# NMX-2017.net
KiCad netlist of a schematic drawn in EAGLE
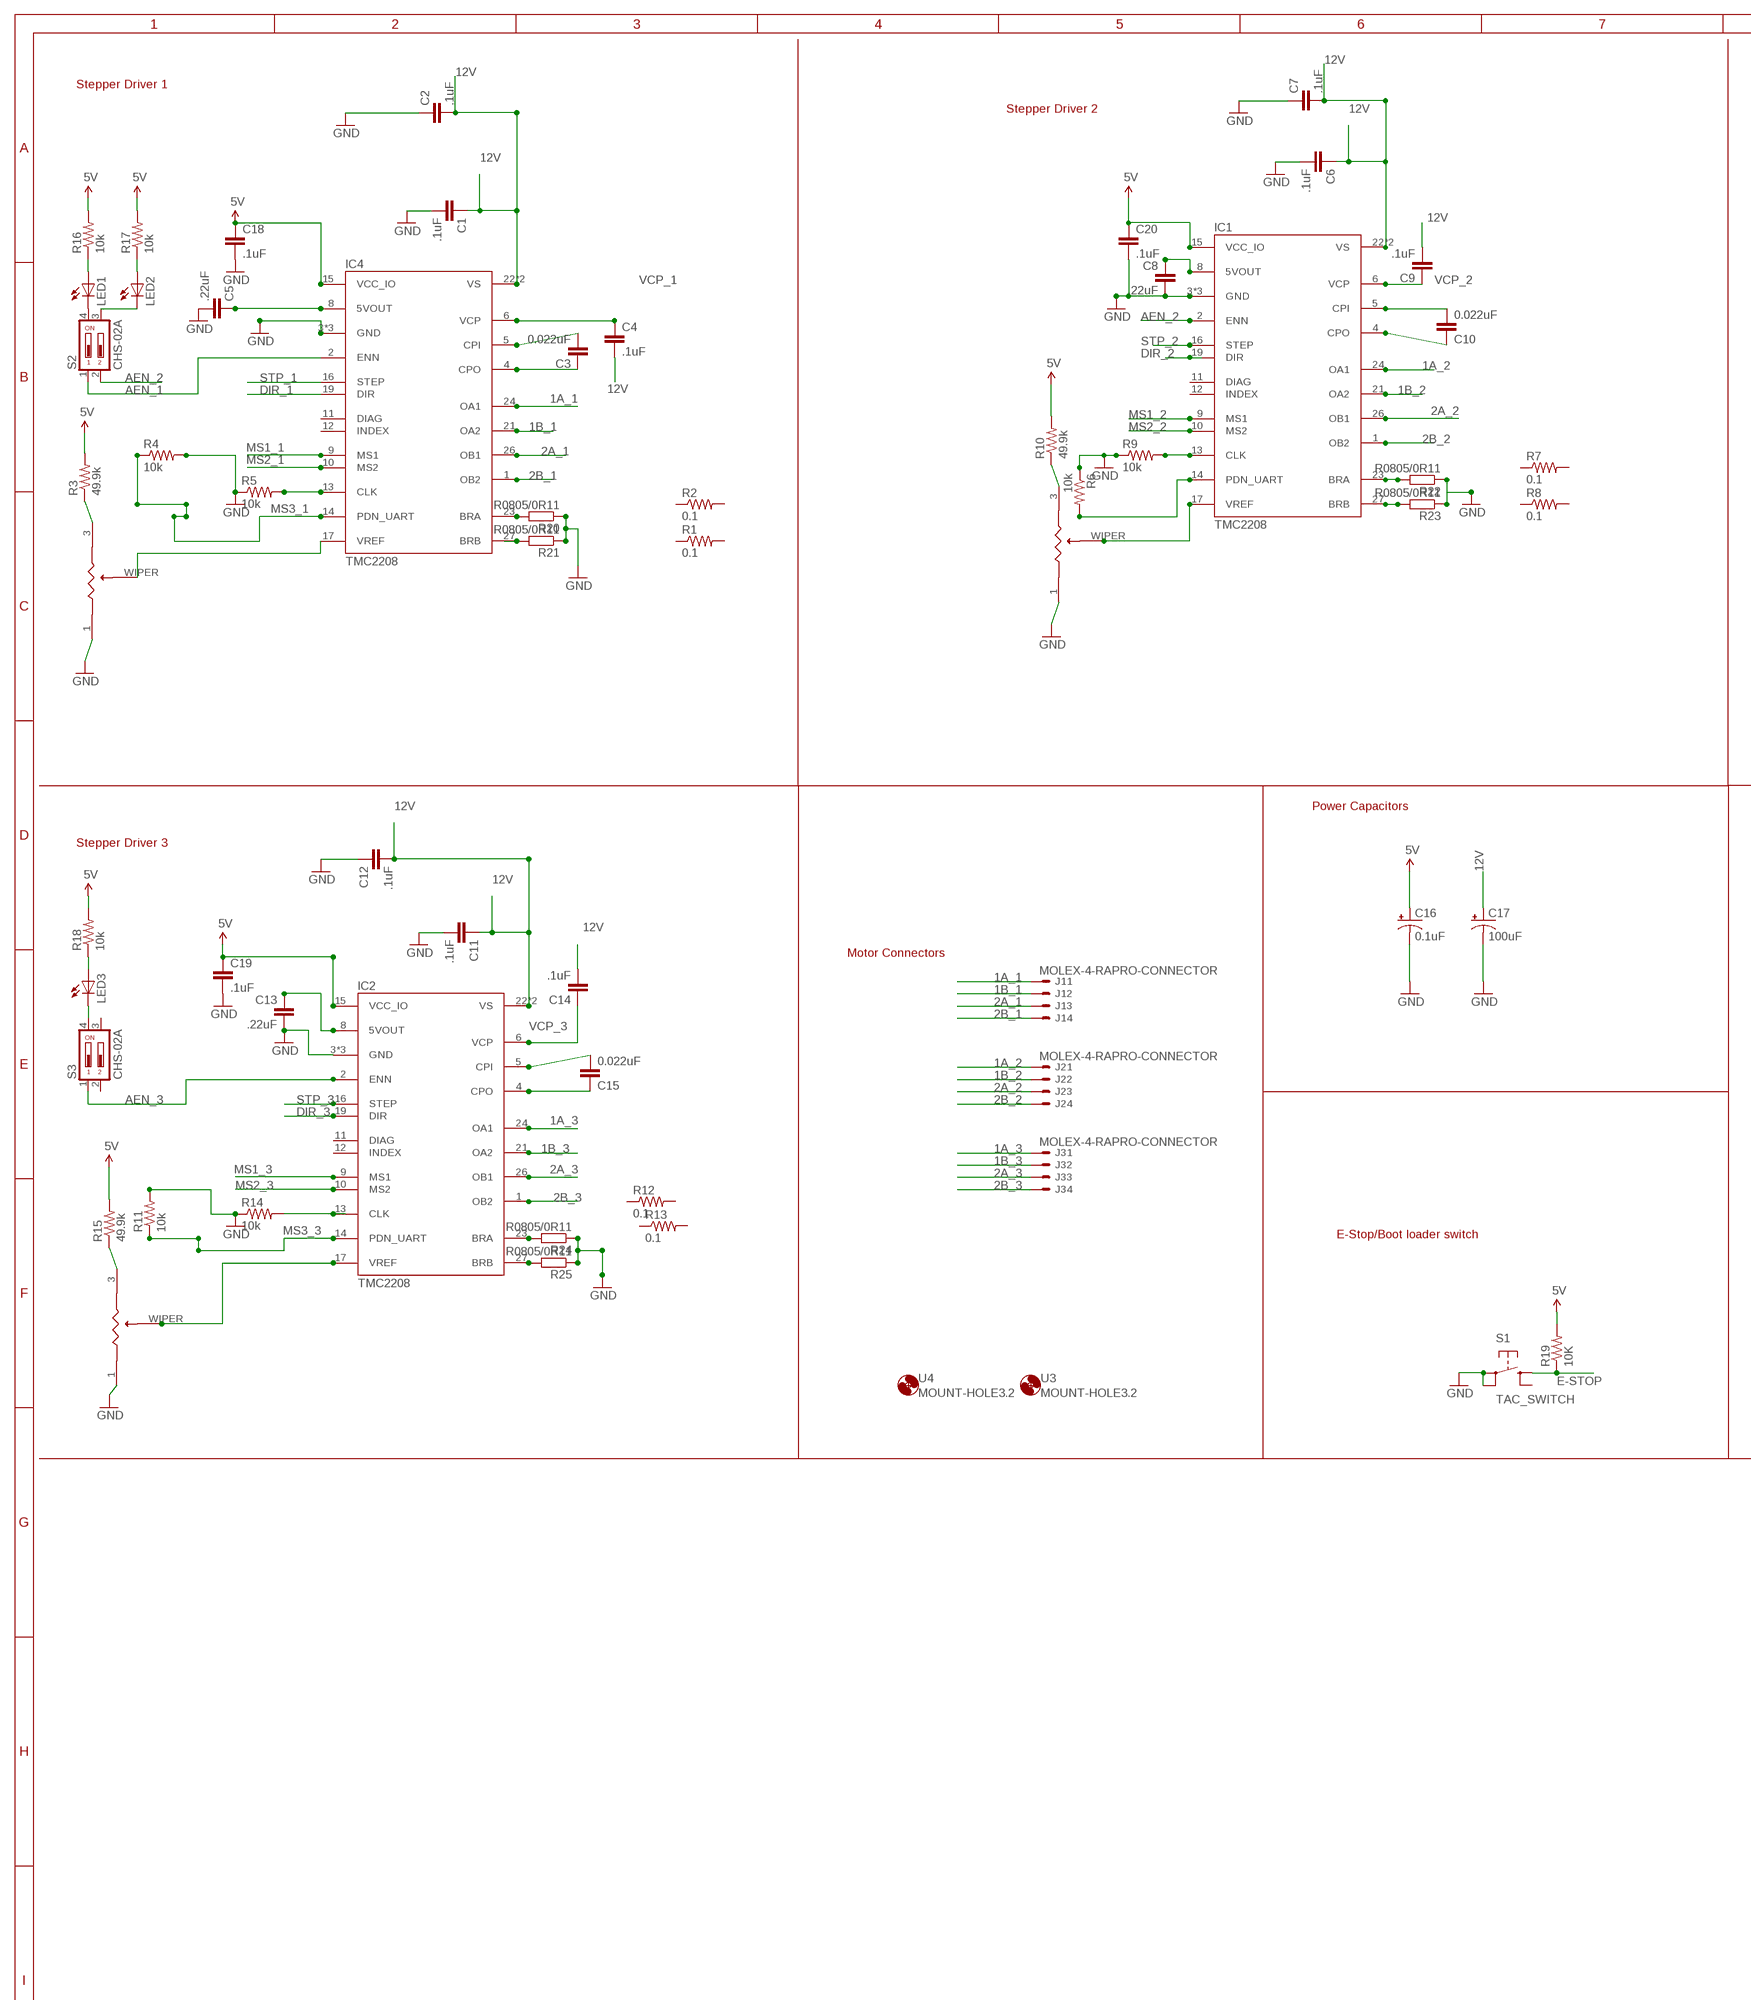
[diagram p0: schematic, sheet 1, part 1 of 2]
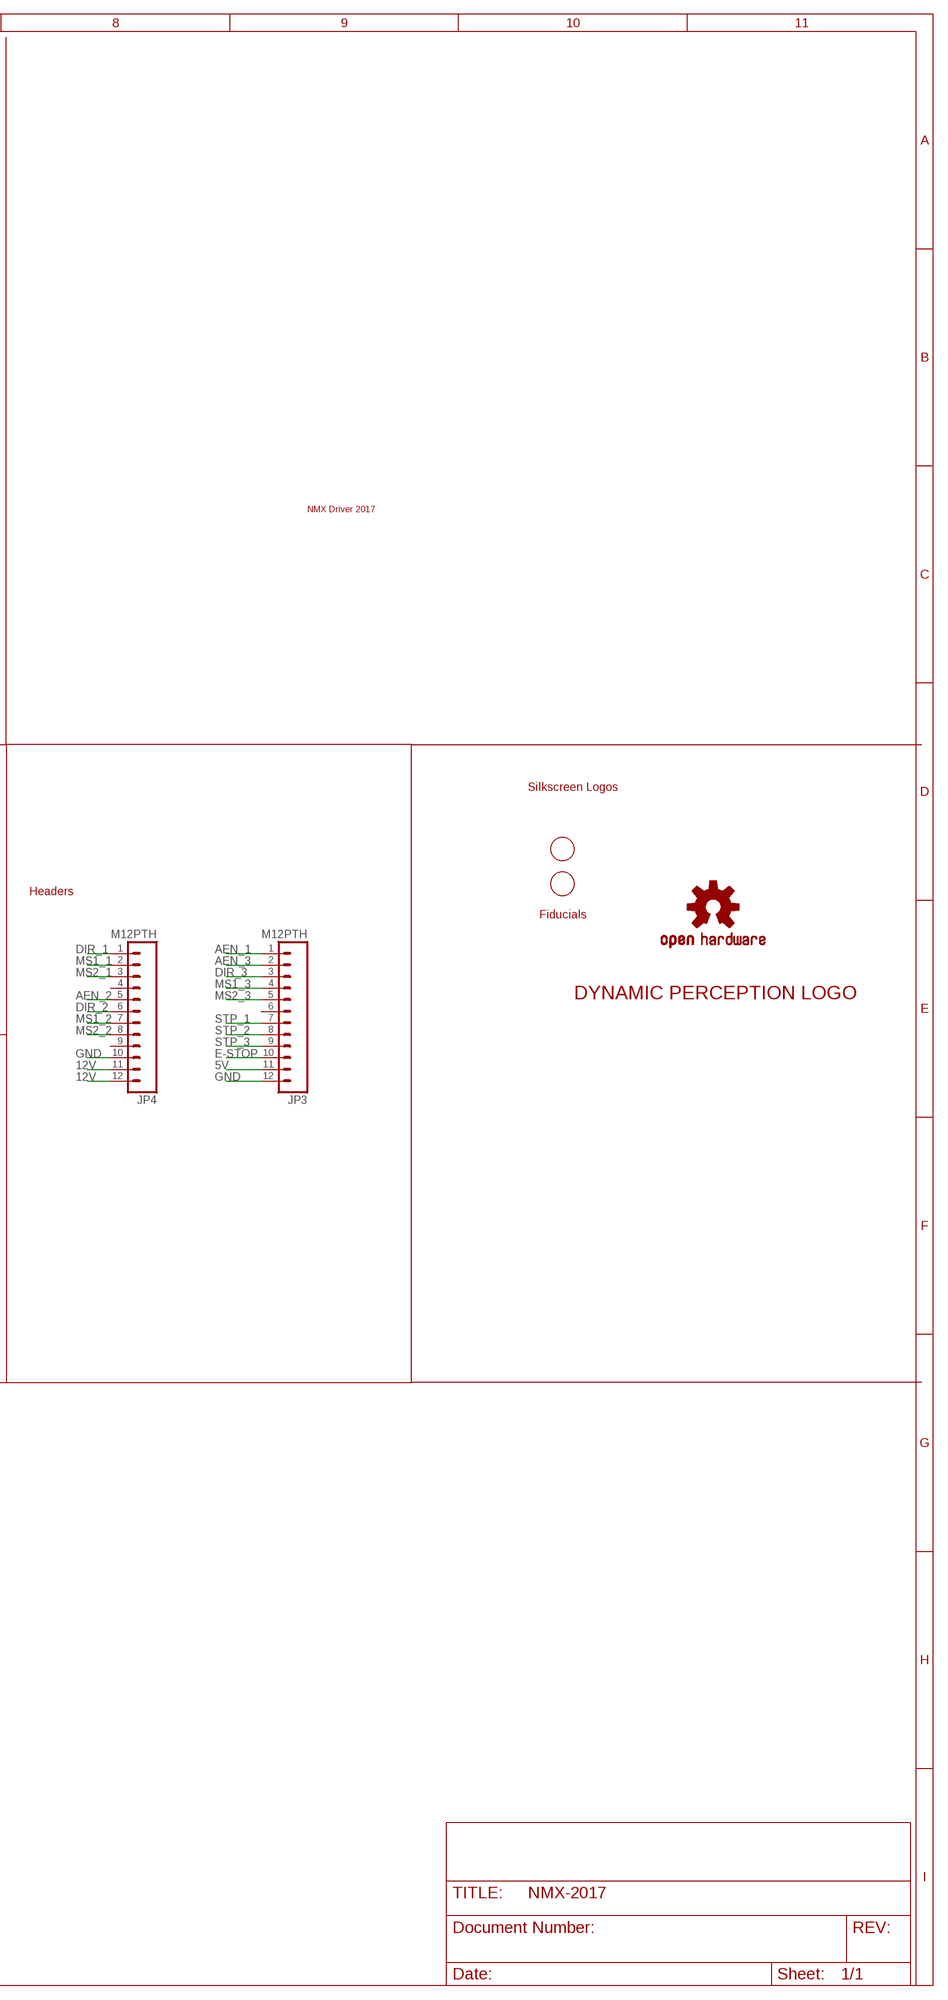
[diagram p1: schematic, sheet 1, part 2 of 2]

(export (version "E")
  (design (tool "Eeschema 10.0.6"))
  (components
    (comp (ref "C1")
      (value ".1uF")
      (footprint "eagle-import:0402-CAP")
      (fields (field (name "MF") "Taiyo Yuden") (field (name "MPN") "TMK105BJ104KV-F"))
      (libsource (lib "eagle-import") (part "CAP0402-CAP"))
    )
    (comp (ref "C2")
      (value ".1uF")
      (footprint "eagle-import:0402-CAP")
      (fields (field (name "MF") "Taiyo Yuden") (field (name "MPN") "TMK105BJ104KV-F"))
      (libsource (lib "eagle-import") (part "CAP0402-CAP"))
    )
    (comp (ref "C3")
      (value "0.022uF")
      (footprint "eagle-import:0402-CAP")
      (fields (field (name "MF") "Taiyo Yuden") (field (name "MPN") "TMK105BJ104KV-F"))
      (libsource (lib "eagle-import") (part "CAP0402-CAP"))
    )
    (comp (ref "C4")
      (value ".1uF")
      (footprint "eagle-import:0402-CAP")
      (fields (field (name "MF") "Taiyo Yuden") (field (name "MPN") "TMK105BJ104KV-F"))
      (libsource (lib "eagle-import") (part "CAP0402-CAP"))
    )
    (comp (ref "C5")
      (value ".22uF")
      (footprint "eagle-import:0402-CAP")
      (fields (field (name "MF") "Taiyo Yuden") (field (name "MPN") "TMK105BJ224KVHF"))
      (libsource (lib "eagle-import") (part "CAP0402-CAP"))
    )
    (comp (ref "C6")
      (value ".1uF")
      (footprint "eagle-import:0402-CAP")
      (fields (field (name "MF") "Taiyo Yuden") (field (name "MPN") "TMK105BJ104KV-F"))
      (libsource (lib "eagle-import") (part "CAP0402-CAP"))
    )
    (comp (ref "C7")
      (value ".1uF")
      (footprint "eagle-import:0402-CAP")
      (fields (field (name "MF") "Taiyo Yuden") (field (name "MPN") "TMK105BJ104KV-F"))
      (libsource (lib "eagle-import") (part "CAP0402-CAP"))
    )
    (comp (ref "C8")
      (value ".22uF")
      (footprint "eagle-import:0402-CAP")
      (fields (field (name "MF") "Taiyo Yuden") (field (name "MPN") "TMK105BJ224KVHF"))
      (libsource (lib "eagle-import") (part "CAP0402-CAP"))
    )
    (comp (ref "C9")
      (value ".1uF")
      (footprint "eagle-import:0402-CAP")
      (fields (field (name "MF") "Taiyo Yuden") (field (name "MPN") "TMK105BJ104KV-F"))
      (libsource (lib "eagle-import") (part "CAP0402-CAP"))
    )
    (comp (ref "C10")
      (value "0.022uF")
      (footprint "eagle-import:0402-CAP")
      (fields (field (name "MF") "Taiyo Yuden") (field (name "MPN") "TMK105BJ104KV-F"))
      (libsource (lib "eagle-import") (part "CAP0402-CAP"))
    )
    (comp (ref "C11")
      (value ".1uF")
      (footprint "eagle-import:0402-CAP")
      (fields (field (name "MF") "Taiyo Yuden") (field (name "MPN") "TMK105BJ104KV-F"))
      (libsource (lib "eagle-import") (part "CAP0402-CAP"))
    )
    (comp (ref "C12")
      (value ".1uF")
      (footprint "eagle-import:0402-CAP")
      (fields (field (name "MF") "Taiyo Yuden") (field (name "MPN") "TMK105BJ104KV-F"))
      (libsource (lib "eagle-import") (part "CAP0402-CAP"))
    )
    (comp (ref "C13")
      (value ".22uF")
      (footprint "eagle-import:0402-CAP")
      (fields (field (name "MF") "Taiyo Yuden") (field (name "MPN") "TMK105BJ224KVHF"))
      (libsource (lib "eagle-import") (part "CAP0402-CAP"))
    )
    (comp (ref "C14")
      (value ".1uF")
      (footprint "eagle-import:0402-CAP")
      (fields (field (name "MF") "Taiyo Yuden") (field (name "MPN") "TMK105BJ104KV-F"))
      (libsource (lib "eagle-import") (part "CAP0402-CAP"))
    )
    (comp (ref "C15")
      (value "0.022uF")
      (footprint "eagle-import:0402-CAP")
      (fields (field (name "MF") "Taiyo Yuden") (field (name "MPN") "TMK105BJ104KV-F"))
      (libsource (lib "eagle-import") (part "CAP0402-CAP"))
    )
    (comp (ref "C16")
      (value "0.1uF")
      (footprint "eagle-import:EIA3216")
      (fields (field (name "MF") "Kemet") (field (name "MPN") "T491A106M016AT"))
      (libsource (lib "eagle-import") (part "CAP_POL1206"))
    )
    (comp (ref "C17")
      (value "100uF")
      (footprint "eagle-import:PANASONIC_D")
      (fields (field (name "MF") "Panasonic Electronic Components") (field (name "MPN") "EEE-1EA101XP"))
      (libsource (lib "eagle-import") (part "CAP_POLD"))
    )
    (comp (ref "C18")
      (value ".1uF")
      (footprint "eagle-import:0402-CAP")
      (fields (field (name "MF") "Taiyo Yuden") (field (name "MPN") "TMK105BJ104KV-F"))
      (libsource (lib "eagle-import") (part "CAP0402-CAP"))
    )
    (comp (ref "C19")
      (value ".1uF")
      (footprint "eagle-import:0402-CAP")
      (fields (field (name "MF") "Taiyo Yuden") (field (name "MPN") "TMK105BJ104KV-F"))
      (libsource (lib "eagle-import") (part "CAP0402-CAP"))
    )
    (comp (ref "C20")
      (value ".1uF")
      (footprint "eagle-import:0402-CAP")
      (fields (field (name "MF") "Taiyo Yuden") (field (name "MPN") "TMK105BJ104KV-F"))
      (libsource (lib "eagle-import") (part "CAP0402-CAP"))
    )
    (comp (ref "IC1")
      (value "TMC2208")
      (footprint "eagle-import:QFN28-PAD")
      (libsource (lib "eagle-import") (part "TMC2208"))
    )
    (comp (ref "IC2")
      (value "TMC2208")
      (footprint "eagle-import:QFN28-PAD")
      (libsource (lib "eagle-import") (part "TMC2208"))
    )
    (comp (ref "IC4")
      (value "TMC2208")
      (footprint "eagle-import:QFN28-PAD")
      (libsource (lib "eagle-import") (part "TMC2208"))
    )
    (comp (ref "J1")
      (value "MOLEX-4-RAPRO-CONNECTOR")
      (footprint "eagle-import:PRO_CONNECTOR")
      (fields (field (name "MF") "Molex Inc") (field (name "MPN") "0022053041"))
      (libsource (lib "eagle-import") (part "MOLEX-4-RAPRO-CONNECTOR"))
    )
    (comp (ref "J2")
      (value "MOLEX-4-RAPRO-CONNECTOR")
      (footprint "eagle-import:PRO_CONNECTOR")
      (fields (field (name "MF") "Molex Inc") (field (name "MPN") "0022053041"))
      (libsource (lib "eagle-import") (part "MOLEX-4-RAPRO-CONNECTOR"))
    )
    (comp (ref "J3")
      (value "MOLEX-4-RAPRO-CONNECTOR")
      (footprint "eagle-import:PRO_CONNECTOR")
      (fields (field (name "MF") "Molex Inc") (field (name "MPN") "0022053041"))
      (libsource (lib "eagle-import") (part "MOLEX-4-RAPRO-CONNECTOR"))
    )
    (comp (ref "JP3")
      (value "M12PTH")
      (footprint "eagle-import:1X12")
      (fields (field (name "MF") "Molex Inc") (field (name "MPN") "0901200132"))
      (libsource (lib "eagle-import") (part "M12PTH"))
    )
    (comp (ref "JP4")
      (value "M12PTH")
      (footprint "eagle-import:1X12")
      (fields (field (name "MF") "Molex Inc") (field (name "MPN") "0901200132"))
      (libsource (lib "eagle-import") (part "M12PTH"))
    )
    (comp (ref "LED1")
      (value "LED0603")
      (footprint "eagle-import:LED-0603")
      (fields (field (name "MF") "OSRAM Opto Semiconductors Inc") (field (name "MPN") "LB Q39G-L2N2-35-1"))
      (libsource (lib "eagle-import") (part "LED0603"))
    )
    (comp (ref "LED2")
      (value "LED0603")
      (footprint "eagle-import:LED-0603")
      (fields (field (name "MF") "OSRAM Opto Semiconductors Inc") (field (name "MPN") "LB Q39G-L2N2-35-1"))
      (libsource (lib "eagle-import") (part "LED0603"))
    )
    (comp (ref "LED3")
      (value "LED0603")
      (footprint "eagle-import:LED-0603")
      (fields (field (name "MF") "OSRAM Opto Semiconductors Inc") (field (name "MPN") "LB Q39G-L2N2-35-1"))
      (libsource (lib "eagle-import") (part "LED0603"))
    )
    (comp (ref "R1")
      (value "0.1")
      (footprint "eagle-import:R0603")
      (fields (field (name "MF") "Samsung Electro-Mechanics America") (field (name "MPN") "RU1608FR100CS"))
      (libsource (lib "eagle-import") (part "R-US_R0603"))
    )
    (comp (ref "R2")
      (value "0.1")
      (footprint "eagle-import:R0603")
      (fields (field (name "MF") "Samsung Electro-Mechanics America") (field (name "MPN") "RU1608FR100CS"))
      (libsource (lib "eagle-import") (part "R-US_R0603"))
    )
    (comp (ref "R3")
      (value "49.9k")
      (footprint "eagle-import:R0402_BOTTOM")
      (fields (field (name "MF") "Yageo") (field (name "MPN") "RC0402FR-0749K9L"))
      (libsource (lib "eagle-import") (part "R-US_R0402_B"))
    )
    (comp (ref "R4")
      (value "10k")
      (footprint "eagle-import:R0402_BOTTOM")
      (fields (field (name "MF") "Yageo") (field (name "MPN") "RC0402FR-0720KL"))
      (libsource (lib "eagle-import") (part "R-US_R0402_B"))
    )
    (comp (ref "R5")
      (value "10k")
      (footprint "eagle-import:R0402_BOTTOM")
      (fields (field (name "MF") "Yageo") (field (name "MPN") "RC0402FR-0720KL"))
      (libsource (lib "eagle-import") (part "R-US_R0402_B"))
    )
    (comp (ref "R6")
      (value "10k")
      (footprint "eagle-import:R0402_BOTTOM")
      (fields (field (name "MF") "Yageo") (field (name "MPN") "RC0402FR-0720KL"))
      (libsource (lib "eagle-import") (part "R-US_R0402_B"))
    )
    (comp (ref "R7")
      (value "0.1")
      (footprint "eagle-import:R0603")
      (fields (field (name "MF") "Samsung Electro-Mechanics America") (field (name "MPN") "RU1608FR100CS"))
      (libsource (lib "eagle-import") (part "R-US_R0603"))
    )
    (comp (ref "R8")
      (value "0.1")
      (footprint "eagle-import:R0603")
      (fields (field (name "MF") "Samsung Electro-Mechanics America") (field (name "MPN") "RU1608FR100CS"))
      (libsource (lib "eagle-import") (part "R-US_R0603"))
    )
    (comp (ref "R9")
      (value "10k")
      (footprint "eagle-import:R0402_BOTTOM")
      (fields (field (name "MF") "Yageo") (field (name "MPN") "RC0402FR-0720KL"))
      (libsource (lib "eagle-import") (part "R-US_R0402_B"))
    )
    (comp (ref "R10")
      (value "49.9k")
      (footprint "eagle-import:R0402_BOTTOM")
      (fields (field (name "MF") "Yageo") (field (name "MPN") "RC0402FR-0749K9L"))
      (libsource (lib "eagle-import") (part "R-US_R0402_B"))
    )
    (comp (ref "R11")
      (value "10k")
      (footprint "eagle-import:R0402_BOTTOM")
      (fields (field (name "MF") "Yageo") (field (name "MPN") "RC0402FR-0720KL"))
      (libsource (lib "eagle-import") (part "R-US_R0402_B"))
    )
    (comp (ref "R12")
      (value "0.1")
      (footprint "eagle-import:R0603")
      (fields (field (name "MF") "Samsung Electro-Mechanics America") (field (name "MPN") "RU1608FR100CS"))
      (libsource (lib "eagle-import") (part "R-US_R0603"))
    )
    (comp (ref "R13")
      (value "0.1")
      (footprint "eagle-import:R0603")
      (fields (field (name "MF") "Samsung Electro-Mechanics America") (field (name "MPN") "RU1608FR100CS"))
      (libsource (lib "eagle-import") (part "R-US_R0603"))
    )
    (comp (ref "R14")
      (value "10k")
      (footprint "eagle-import:R0402_BOTTOM")
      (fields (field (name "MF") "Yageo") (field (name "MPN") "RC0402FR-0720KL"))
      (libsource (lib "eagle-import") (part "R-US_R0402_B"))
    )
    (comp (ref "R15")
      (value "49.9k")
      (footprint "eagle-import:R0402_BOTTOM")
      (fields (field (name "MF") "Yageo") (field (name "MPN") "RC0402FR-0749K9L"))
      (libsource (lib "eagle-import") (part "R-US_R0402_B"))
    )
    (comp (ref "R16")
      (value "10k")
      (footprint "eagle-import:R0402_BOTTOM")
      (fields (field (name "MF") "Yageo") (field (name "MPN") "RC0402FR-0714KL"))
      (libsource (lib "eagle-import") (part "R-US_R0402_B"))
    )
    (comp (ref "R17")
      (value "10k")
      (footprint "eagle-import:R0402_BOTTOM")
      (fields (field (name "MF") "Yageo") (field (name "MPN") "RC0402FR-0714KL"))
      (libsource (lib "eagle-import") (part "R-US_R0402_B"))
    )
    (comp (ref "R18")
      (value "10k")
      (footprint "eagle-import:R0402_BOTTOM")
      (fields (field (name "MF") "Yageo") (field (name "MPN") "RC0402FR-0714KL"))
      (libsource (lib "eagle-import") (part "R-US_R0402_B"))
    )
    (comp (ref "R19")
      (value "10K")
      (footprint "eagle-import:R0402_BOTTOM")
      (fields (field (name "MF") "Yageo") (field (name "MPN") "RC0402FR-0710KL"))
      (libsource (lib "eagle-import") (part "R-US_R0402_B"))
    )
    (comp (ref "R20")
      (value "R0805/0R11")
      (footprint "eagle-import:M0805")
      (libsource (lib "eagle-import") (part "R-EU_M0805"))
    )
    (comp (ref "R21")
      (value "R0805/0R11")
      (footprint "eagle-import:M0805")
      (libsource (lib "eagle-import") (part "R-EU_M0805"))
    )
    (comp (ref "R22")
      (value "R0805/0R11")
      (footprint "eagle-import:M0805")
      (libsource (lib "eagle-import") (part "R-EU_M0805"))
    )
    (comp (ref "R23")
      (value "R0805/0R11")
      (footprint "eagle-import:M0805")
      (libsource (lib "eagle-import") (part "R-EU_M0805"))
    )
    (comp (ref "R24")
      (value "R0805/0R11")
      (footprint "eagle-import:M0805")
      (libsource (lib "eagle-import") (part "R-EU_M0805"))
    )
    (comp (ref "R25")
      (value "R0805/0R11")
      (footprint "eagle-import:M0805")
      (libsource (lib "eagle-import") (part "R-EU_M0805"))
    )
    (comp (ref "S1")
      (value "TAC_SWITCH")
      (footprint "eagle-import:TAC_SWITCH_THR")
      (fields (field (name "MF") "TE Connectivity") (field (name "MPN") "2-1825027-0"))
      (libsource (lib "eagle-import") (part "TAC_SWITCH"))
    )
    (comp (ref "S2")
      (value "CHS-02A")
      (footprint "eagle-import:CHS-02A")
      (libsource (lib "eagle-import") (part "CHS-02A"))
    )
    (comp (ref "S3")
      (value "CHS-02A")
      (footprint "eagle-import:CHS-02A")
      (libsource (lib "eagle-import") (part "CHS-02A"))
    )
    (comp (ref "U$1")
      (value "DP_LOGOMICRO")
      (footprint "eagle-import:DP_LOGO_MICRO")
      (libsource (lib "eagle-import") (part "DP_LOGOMICRO"))
    )
    (comp (ref "U$2")
      (value "OSHW-LOGOS")
      (footprint "eagle-import:OSHW-LOGO-S")
      (libsource (lib "eagle-import") (part "OSHW-LOGOS"))
    )
    (comp (ref "U$3")
      (value "FIDUCIAL")
      (footprint "eagle-import:FIDUCIAL_1MM")
      (libsource (lib "eagle-import") (part "FIDUCIAL"))
    )
    (comp (ref "U$4")
      (value "FIDUCIAL")
      (footprint "eagle-import:FIDUCIAL_1MM")
      (libsource (lib "eagle-import") (part "FIDUCIAL"))
    )
    (comp (ref "U1")
      (value "CADJ")
      (footprint "eagle-import:3MM_SMD")
      (fields (field (name "MF") "Bourns Inc") (field (name "MPN") "TC33X-2-103E"))
      (libsource (lib "eagle-import") (part "TC33X-2"))
    )
    (comp (ref "U2")
      (value "CADJ")
      (footprint "eagle-import:3MM_SMD")
      (fields (field (name "MF") "Bourns Inc") (field (name "MPN") "TC33X-2-103E"))
      (libsource (lib "eagle-import") (part "TC33X-2"))
    )
    (comp (ref "U3")
      (value "MOUNT-HOLE3.2")
      (footprint "eagle-import:3,2")
      (libsource (lib "eagle-import") (part "MOUNT-HOLE3.2"))
    )
    (comp (ref "U4")
      (value "MOUNT-HOLE3.2")
      (footprint "eagle-import:3,2")
      (libsource (lib "eagle-import") (part "MOUNT-HOLE3.2"))
    )
    (comp (ref "U5")
      (value "CADJ")
      (footprint "eagle-import:3MM_SMD")
      (fields (field (name "MF") "Bourns Inc") (field (name "MPN") "TC33X-2-103E"))
      (libsource (lib "eagle-import") (part "TC33X-2"))
    )
  )
  (nets
    (net (code "1") (name "/1A_1") (class "Default")
      (node (ref "IC4") (pin "24") (pinfunction "OA1_24") (pintype "output"))
      (node (ref "J1") (pin "P$1") (pinfunction "S_P$1") (pintype "passive"))
    )
    (net (code "2") (name "/1A_2") (class "Default")
      (node (ref "IC1") (pin "24") (pinfunction "OA1_24") (pintype "output"))
      (node (ref "J2") (pin "P$1") (pinfunction "S_P$1") (pintype "passive"))
    )
    (net (code "3") (name "/1A_3") (class "Default")
      (node (ref "IC2") (pin "24") (pinfunction "OA1_24") (pintype "output"))
      (node (ref "J3") (pin "P$1") (pinfunction "S_P$1") (pintype "passive"))
    )
    (net (code "4") (name "/1B_1") (class "Default")
      (node (ref "IC4") (pin "21") (pinfunction "OA2_21") (pintype "output"))
      (node (ref "J1") (pin "P$2") (pinfunction "S_P$2") (pintype "passive"))
    )
    (net (code "5") (name "/1B_2") (class "Default")
      (node (ref "IC1") (pin "21") (pinfunction "OA2_21") (pintype "output"))
      (node (ref "J2") (pin "P$2") (pinfunction "S_P$2") (pintype "passive"))
    )
    (net (code "6") (name "/1B_3") (class "Default")
      (node (ref "IC2") (pin "21") (pinfunction "OA2_21") (pintype "output"))
      (node (ref "J3") (pin "P$2") (pinfunction "S_P$2") (pintype "passive"))
    )
    (net (code "7") (name "/2A_1") (class "Default")
      (node (ref "IC4") (pin "26") (pinfunction "OB1_26") (pintype "output"))
      (node (ref "J1") (pin "P$3") (pinfunction "S_P$3") (pintype "passive"))
    )
    (net (code "8") (name "/2A_2") (class "Default")
      (node (ref "IC1") (pin "26") (pinfunction "OB1_26") (pintype "output"))
      (node (ref "J2") (pin "P$3") (pinfunction "S_P$3") (pintype "passive"))
    )
    (net (code "9") (name "/2A_3") (class "Default")
      (node (ref "IC2") (pin "26") (pinfunction "OB1_26") (pintype "output"))
      (node (ref "J3") (pin "P$3") (pinfunction "S_P$3") (pintype "passive"))
    )
    (net (code "10") (name "/2B_1") (class "Default")
      (node (ref "IC4") (pin "1") (pinfunction "OB2_1") (pintype "output"))
      (node (ref "J1") (pin "P$4") (pinfunction "S_P$4") (pintype "passive"))
    )
    (net (code "11") (name "/2B_2") (class "Default")
      (node (ref "IC1") (pin "1") (pinfunction "OB2_1") (pintype "output"))
      (node (ref "J2") (pin "P$4") (pinfunction "S_P$4") (pintype "passive"))
    )
    (net (code "12") (name "/2B_3") (class "Default")
      (node (ref "IC2") (pin "1") (pinfunction "OB2_1") (pintype "output"))
      (node (ref "J3") (pin "P$4") (pinfunction "S_P$4") (pintype "passive"))
    )
    (net (code "13") (name "/12V") (class "Default")
      (node (ref "C1") (pin "1") (pinfunction "1_1") (pintype "passive"))
      (node (ref "C11") (pin "1") (pinfunction "1_1") (pintype "passive"))
      (node (ref "C12") (pin "2") (pinfunction "2_2") (pintype "passive"))
      (node (ref "C14") (pin "2") (pinfunction "2_2") (pintype "passive"))
      (node (ref "C17") (pin "+") (pinfunction "+_+") (pintype "passive"))
      (node (ref "C2") (pin "2") (pinfunction "2_2") (pintype "passive"))
      (node (ref "C4") (pin "2") (pinfunction "2_2") (pintype "passive"))
      (node (ref "C6") (pin "1") (pinfunction "1_1") (pintype "passive"))
      (node (ref "C7") (pin "2") (pinfunction "2_2") (pintype "passive"))
      (node (ref "C9") (pin "2") (pinfunction "2_2") (pintype "passive"))
      (node (ref "IC1") (pin "22") (pinfunction "VS_22") (pintype "power_in"))
      (node (ref "IC1") (pin "28") (pinfunction "VS_28") (pintype "power_in"))
      (node (ref "IC2") (pin "22") (pinfunction "VS_22") (pintype "power_in"))
      (node (ref "IC2") (pin "28") (pinfunction "VS_28") (pintype "power_in"))
      (node (ref "IC4") (pin "22") (pinfunction "VS_22") (pintype "power_in"))
      (node (ref "IC4") (pin "28") (pinfunction "VS_28") (pintype "power_in"))
      (node (ref "JP4") (pin "11") (pinfunction "11_11") (pintype "passive"))
      (node (ref "JP4") (pin "12") (pinfunction "12_12") (pintype "passive"))
    )
    (net (code "14") (name "/AEN_1") (class "Default")
      (node (ref "IC4") (pin "2") (pinfunction "ENN_2") (pintype "bidirectional"))
      (node (ref "JP3") (pin "1") (pinfunction "1_1") (pintype "passive"))
      (node (ref "S2") (pin "1") (pinfunction "1_1") (pintype "passive"))
    )
    (net (code "15") (name "/AEN_2") (class "Default")
      (node (ref "IC1") (pin "2") (pinfunction "ENN_2") (pintype "bidirectional"))
      (node (ref "JP4") (pin "5") (pinfunction "5_5") (pintype "passive"))
      (node (ref "S2") (pin "2") (pinfunction "2_2") (pintype "passive"))
    )
    (net (code "16") (name "/AEN_3") (class "Default")
      (node (ref "IC2") (pin "2") (pinfunction "ENN_2") (pintype "bidirectional"))
      (node (ref "JP3") (pin "2") (pinfunction "2_2") (pintype "passive"))
      (node (ref "S3") (pin "1") (pinfunction "1_1") (pintype "passive"))
    )
    (net (code "17") (name "/DIR_1") (class "Default")
      (node (ref "IC4") (pin "19") (pinfunction "DIR_19") (pintype "bidirectional"))
      (node (ref "JP4") (pin "1") (pinfunction "1_1") (pintype "passive"))
    )
    (net (code "18") (name "/DIR_2") (class "Default")
      (node (ref "IC1") (pin "19") (pinfunction "DIR_19") (pintype "bidirectional"))
      (node (ref "JP4") (pin "6") (pinfunction "6_6") (pintype "passive"))
    )
    (net (code "19") (name "/DIR_3") (class "Default")
      (node (ref "IC2") (pin "19") (pinfunction "DIR_19") (pintype "bidirectional"))
      (node (ref "JP3") (pin "3") (pinfunction "3_3") (pintype "passive"))
    )
    (net (code "20") (name "/E-STOP") (class "Default")
      (node (ref "JP3") (pin "10") (pinfunction "10_10") (pintype "passive"))
      (node (ref "R19") (pin "1") (pinfunction "1_1") (pintype "passive"))
      (node (ref "S1") (pin "B") (pinfunction "3_B") (pintype "passive"))
    )
    (net (code "21") (name "/MS1_1") (class "Default")
      (node (ref "IC4") (pin "9") (pinfunction "MS1_9") (pintype "bidirectional"))
      (node (ref "JP4") (pin "2") (pinfunction "2_2") (pintype "passive"))
    )
    (net (code "22") (name "/MS1_2") (class "Default")
      (node (ref "IC1") (pin "9") (pinfunction "MS1_9") (pintype "bidirectional"))
      (node (ref "JP4") (pin "7") (pinfunction "7_7") (pintype "passive"))
    )
    (net (code "23") (name "/MS1_3") (class "Default")
      (node (ref "IC2") (pin "9") (pinfunction "MS1_9") (pintype "bidirectional"))
      (node (ref "JP3") (pin "4") (pinfunction "4_4") (pintype "passive"))
    )
    (net (code "24") (name "/MS2_1") (class "Default")
      (node (ref "IC4") (pin "10") (pinfunction "MS2_10") (pintype "bidirectional"))
      (node (ref "JP4") (pin "3") (pinfunction "3_3") (pintype "passive"))
    )
    (net (code "25") (name "/MS2_2") (class "Default")
      (node (ref "IC1") (pin "10") (pinfunction "MS2_10") (pintype "bidirectional"))
      (node (ref "JP4") (pin "8") (pinfunction "8_8") (pintype "passive"))
    )
    (net (code "26") (name "/MS2_3") (class "Default")
      (node (ref "IC2") (pin "10") (pinfunction "MS2_10") (pintype "bidirectional"))
      (node (ref "JP3") (pin "5") (pinfunction "5_5") (pintype "passive"))
    )
    (net (code "27") (name "/MS3_1") (class "Default")
      (node (ref "IC4") (pin "14") (pinfunction "PDN_UART_14") (pintype "bidirectional"))
      (node (ref "R4") (pin "1") (pinfunction "1_1") (pintype "passive"))
    )
    (net (code "28") (name "/MS3_3") (class "Default")
      (node (ref "IC2") (pin "14") (pinfunction "PDN_UART_14") (pintype "bidirectional"))
      (node (ref "R11") (pin "1") (pinfunction "1_1") (pintype "passive"))
    )
    (net (code "29") (name "/STP_1") (class "Default")
      (node (ref "IC4") (pin "16") (pinfunction "STEP_16") (pintype "bidirectional"))
      (node (ref "JP3") (pin "7") (pinfunction "7_7") (pintype "passive"))
    )
    (net (code "30") (name "/STP_2") (class "Default")
      (node (ref "IC1") (pin "16") (pinfunction "STEP_16") (pintype "bidirectional"))
      (node (ref "JP3") (pin "8") (pinfunction "8_8") (pintype "passive"))
    )
    (net (code "31") (name "/STP_3") (class "Default")
      (node (ref "IC2") (pin "16") (pinfunction "STEP_16") (pintype "bidirectional"))
      (node (ref "JP3") (pin "9") (pinfunction "9_9") (pintype "passive"))
    )
    (net (code "32") (name "/VCP_1") (class "Default")
      (node (ref "C4") (pin "1") (pinfunction "1_1") (pintype "passive"))
      (node (ref "IC4") (pin "6") (pinfunction "VCP_6") (pintype "passive"))
    )
    (net (code "33") (name "/VCP_2") (class "Default")
      (node (ref "C9") (pin "1") (pinfunction "1_1") (pintype "passive"))
      (node (ref "IC1") (pin "6") (pinfunction "VCP_6") (pintype "passive"))
    )
    (net (code "34") (name "/VCP_3") (class "Default")
      (node (ref "C14") (pin "1") (pinfunction "1_1") (pintype "passive"))
      (node (ref "IC2") (pin "6") (pinfunction "VCP_6") (pintype "passive"))
    )
    (net (code "35") (name "5V") (class "Default")
      (node (ref "C16") (pin "A") (pinfunction "+_A") (pintype "passive"))
      (node (ref "C18") (pin "1") (pinfunction "1_1") (pintype "passive"))
      (node (ref "C19") (pin "1") (pinfunction "1_1") (pintype "passive"))
      (node (ref "C20") (pin "1") (pinfunction "1_1") (pintype "passive"))
      (node (ref "IC1") (pin "15") (pinfunction "VCC_IO_15") (pintype "power_in"))
      (node (ref "IC2") (pin "15") (pinfunction "VCC_IO_15") (pintype "power_in"))
      (node (ref "IC4") (pin "15") (pinfunction "VCC_IO_15") (pintype "power_in"))
      (node (ref "JP3") (pin "11") (pinfunction "11_11") (pintype "passive"))
      (node (ref "R10") (pin "2") (pinfunction "2_2") (pintype "passive"))
      (node (ref "R15") (pin "2") (pinfunction "2_2") (pintype "passive"))
      (node (ref "R16") (pin "2") (pinfunction "2_2") (pintype "passive"))
      (node (ref "R17") (pin "2") (pinfunction "2_2") (pintype "passive"))
      (node (ref "R18") (pin "2") (pinfunction "2_2") (pintype "passive"))
      (node (ref "R19") (pin "2") (pinfunction "2_2") (pintype "passive"))
      (node (ref "R3") (pin "2") (pinfunction "2_2") (pintype "passive"))
    )
    (net (code "36") (name "GND") (class "Default")
      (node (ref "C1") (pin "2") (pinfunction "2_2") (pintype "passive"))
      (node (ref "C11") (pin "2") (pinfunction "2_2") (pintype "passive"))
      (node (ref "C12") (pin "1") (pinfunction "1_1") (pintype "passive"))
      (node (ref "C13") (pin "2") (pinfunction "2_2") (pintype "passive"))
      (node (ref "C16") (pin "C") (pinfunction "-_C") (pintype "passive"))
      (node (ref "C17") (pin "-") (pinfunction "-_-") (pintype "passive"))
      (node (ref "C18") (pin "2") (pinfunction "2_2") (pintype "passive"))
      (node (ref "C19") (pin "2") (pinfunction "2_2") (pintype "passive"))
      (node (ref "C2") (pin "1") (pinfunction "1_1") (pintype "passive"))
      (node (ref "C20") (pin "2") (pinfunction "2_2") (pintype "passive"))
      (node (ref "C5") (pin "2") (pinfunction "2_2") (pintype "passive"))
      (node (ref "C6") (pin "2") (pinfunction "2_2") (pintype "passive"))
      (node (ref "C7") (pin "1") (pinfunction "1_1") (pintype "passive"))
      (node (ref "C8") (pin "2") (pinfunction "2_2") (pintype "passive"))
      (node (ref "IC1") (pin "18") (pinfunction "GND_18") (pintype "power_in"))
      (node (ref "IC1") (pin "3") (pinfunction "GND_3") (pintype "power_in"))
      (node (ref "IC1") (pin "TP") (pinfunction "GND_TP") (pintype "power_in"))
      (node (ref "IC2") (pin "18") (pinfunction "GND_18") (pintype "power_in"))
      (node (ref "IC2") (pin "3") (pinfunction "GND_3") (pintype "power_in"))
      (node (ref "IC2") (pin "TP") (pinfunction "GND_TP") (pintype "power_in"))
      (node (ref "IC4") (pin "18") (pinfunction "GND_18") (pintype "power_in"))
      (node (ref "IC4") (pin "3") (pinfunction "GND_3") (pintype "power_in"))
      (node (ref "IC4") (pin "TP") (pinfunction "GND_TP") (pintype "power_in"))
      (node (ref "JP3") (pin "12") (pinfunction "12_12") (pintype "passive"))
      (node (ref "JP4") (pin "10") (pinfunction "10_10") (pintype "passive"))
      (node (ref "R11") (pin "2") (pinfunction "2_2") (pintype "passive"))
      (node (ref "R14") (pin "1") (pinfunction "1_1") (pintype "passive"))
      (node (ref "R20") (pin "1") (pinfunction "1_1") (pintype "passive"))
      (node (ref "R21") (pin "1") (pinfunction "1_1") (pintype "passive"))
      (node (ref "R22") (pin "1") (pinfunction "1_1") (pintype "passive"))
      (node (ref "R23") (pin "1") (pinfunction "1_1") (pintype "passive"))
      (node (ref "R24") (pin "1") (pinfunction "1_1") (pintype "passive"))
      (node (ref "R25") (pin "1") (pinfunction "1_1") (pintype "passive"))
      (node (ref "R4") (pin "2") (pinfunction "2_2") (pintype "passive"))
      (node (ref "R5") (pin "1") (pinfunction "1_1") (pintype "passive"))
      (node (ref "R6") (pin "1") (pinfunction "1_1") (pintype "passive"))
      (node (ref "R9") (pin "1") (pinfunction "1_1") (pintype "passive"))
      (node (ref "S1") (pin "A") (pinfunction "1_A") (pintype "passive"))
      (node (ref "S1") (pin "P$1") (pinfunction "2_P$1") (pintype "passive"))
      (node (ref "U1") (pin "1") (pinfunction "1_1") (pintype "bidirectional"))
      (node (ref "U2") (pin "1") (pinfunction "1_1") (pintype "bidirectional"))
      (node (ref "U5") (pin "1") (pinfunction "1_1") (pintype "bidirectional"))
    )
    (net (code "37") (name "Net-(IC1-5VOUT)") (class "Default")
      (node (ref "C8") (pin "1") (pinfunction "1_1") (pintype "passive"))
      (node (ref "IC1") (pin "8") (pinfunction "5VOUT_8") (pintype "power_in"))
    )
    (net (code "38") (name "Net-(IC1-BRA)") (class "Default")
      (node (ref "IC1") (pin "23") (pinfunction "BRA_23") (pintype "output"))
      (node (ref "R22") (pin "2") (pinfunction "2_2") (pintype "passive"))
    )
    (net (code "39") (name "Net-(IC1-BRB)") (class "Default")
      (node (ref "IC1") (pin "27") (pinfunction "BRB_27") (pintype "output"))
      (node (ref "R23") (pin "2") (pinfunction "2_2") (pintype "passive"))
    )
    (net (code "40") (name "Net-(IC1-CLK)") (class "Default")
      (node (ref "IC1") (pin "13") (pinfunction "CLK_13") (pintype "bidirectional"))
      (node (ref "R9") (pin "2") (pinfunction "2_2") (pintype "passive"))
    )
    (net (code "41") (name "Net-(IC1-CPI)") (class "Default")
      (node (ref "C10") (pin "2") (pinfunction "2_2") (pintype "passive"))
      (node (ref "IC1") (pin "5") (pinfunction "CPI_5") (pintype "passive"))
    )
    (net (code "42") (name "Net-(IC1-CPO)") (class "Default")
      (node (ref "C10") (pin "1") (pinfunction "1_1") (pintype "passive"))
      (node (ref "IC1") (pin "4") (pinfunction "CPO_4") (pintype "passive"))
    )
    (net (code "43") (name "Net-(IC1-PDN_UART)") (class "Default")
      (node (ref "IC1") (pin "14") (pinfunction "PDN_UART_14") (pintype "bidirectional"))
      (node (ref "R6") (pin "2") (pinfunction "2_2") (pintype "passive"))
    )
    (net (code "44") (name "Net-(IC1-VREF)") (class "Default")
      (node (ref "IC1") (pin "17") (pinfunction "VREF_17") (pintype "passive"))
      (node (ref "U2") (pin "WIPER") (pinfunction "2_WIPER") (pintype "bidirectional"))
    )
    (net (code "45") (name "Net-(IC2-5VOUT)") (class "Default")
      (node (ref "C13") (pin "1") (pinfunction "1_1") (pintype "passive"))
      (node (ref "IC2") (pin "8") (pinfunction "5VOUT_8") (pintype "power_in"))
    )
    (net (code "46") (name "Net-(IC2-BRA)") (class "Default")
      (node (ref "IC2") (pin "23") (pinfunction "BRA_23") (pintype "output"))
      (node (ref "R24") (pin "2") (pinfunction "2_2") (pintype "passive"))
    )
    (net (code "47") (name "Net-(IC2-BRB)") (class "Default")
      (node (ref "IC2") (pin "27") (pinfunction "BRB_27") (pintype "output"))
      (node (ref "R25") (pin "2") (pinfunction "2_2") (pintype "passive"))
    )
    (net (code "48") (name "Net-(IC2-CLK)") (class "Default")
      (node (ref "IC2") (pin "13") (pinfunction "CLK_13") (pintype "bidirectional"))
      (node (ref "R14") (pin "2") (pinfunction "2_2") (pintype "passive"))
    )
    (net (code "49") (name "Net-(IC2-CPI)") (class "Default")
      (node (ref "C15") (pin "2") (pinfunction "2_2") (pintype "passive"))
      (node (ref "IC2") (pin "5") (pinfunction "CPI_5") (pintype "passive"))
    )
    (net (code "50") (name "Net-(IC2-CPO)") (class "Default")
      (node (ref "C15") (pin "1") (pinfunction "1_1") (pintype "passive"))
      (node (ref "IC2") (pin "4") (pinfunction "CPO_4") (pintype "passive"))
    )
    (net (code "51") (name "Net-(IC2-VREF)") (class "Default")
      (node (ref "IC2") (pin "17") (pinfunction "VREF_17") (pintype "passive"))
      (node (ref "U5") (pin "WIPER") (pinfunction "2_WIPER") (pintype "bidirectional"))
    )
    (net (code "52") (name "Net-(IC4-5VOUT)") (class "Default")
      (node (ref "C5") (pin "1") (pinfunction "1_1") (pintype "passive"))
      (node (ref "IC4") (pin "8") (pinfunction "5VOUT_8") (pintype "power_in"))
    )
    (net (code "53") (name "Net-(IC4-BRA)") (class "Default")
      (node (ref "IC4") (pin "23") (pinfunction "BRA_23") (pintype "output"))
      (node (ref "R20") (pin "2") (pinfunction "2_2") (pintype "passive"))
    )
    (net (code "54") (name "Net-(IC4-BRB)") (class "Default")
      (node (ref "IC4") (pin "27") (pinfunction "BRB_27") (pintype "output"))
      (node (ref "R21") (pin "2") (pinfunction "2_2") (pintype "passive"))
    )
    (net (code "55") (name "Net-(IC4-CLK)") (class "Default")
      (node (ref "IC4") (pin "13") (pinfunction "CLK_13") (pintype "bidirectional"))
      (node (ref "R5") (pin "2") (pinfunction "2_2") (pintype "passive"))
    )
    (net (code "56") (name "Net-(IC4-CPI)") (class "Default")
      (node (ref "C3") (pin "2") (pinfunction "2_2") (pintype "passive"))
      (node (ref "IC4") (pin "5") (pinfunction "CPI_5") (pintype "passive"))
    )
    (net (code "57") (name "Net-(IC4-CPO)") (class "Default")
      (node (ref "C3") (pin "1") (pinfunction "1_1") (pintype "passive"))
      (node (ref "IC4") (pin "4") (pinfunction "CPO_4") (pintype "passive"))
    )
    (net (code "58") (name "Net-(IC4-VREF)") (class "Default")
      (node (ref "IC4") (pin "17") (pinfunction "VREF_17") (pintype "passive"))
      (node (ref "U1") (pin "WIPER") (pinfunction "2_WIPER") (pintype "bidirectional"))
    )
    (net (code "59") (name "Net-(LED1-PadA)") (class "Default")
      (node (ref "LED1") (pin "A") (pinfunction "A_A") (pintype "passive"))
      (node (ref "R16") (pin "1") (pinfunction "1_1") (pintype "passive"))
    )
    (net (code "60") (name "Net-(LED1-PadC)") (class "Default")
      (node (ref "LED1") (pin "C") (pinfunction "C_C") (pintype "passive"))
      (node (ref "S2") (pin "4") (pinfunction "4_4") (pintype "passive"))
    )
    (net (code "61") (name "Net-(LED2-PadA)") (class "Default")
      (node (ref "LED2") (pin "A") (pinfunction "A_A") (pintype "passive"))
      (node (ref "R17") (pin "1") (pinfunction "1_1") (pintype "passive"))
    )
    (net (code "62") (name "Net-(LED2-PadC)") (class "Default")
      (node (ref "LED2") (pin "C") (pinfunction "C_C") (pintype "passive"))
      (node (ref "S2") (pin "3") (pinfunction "3_3") (pintype "passive"))
    )
    (net (code "63") (name "Net-(LED3-PadA)") (class "Default")
      (node (ref "LED3") (pin "A") (pinfunction "A_A") (pintype "passive"))
      (node (ref "R18") (pin "1") (pinfunction "1_1") (pintype "passive"))
    )
    (net (code "64") (name "Net-(LED3-PadC)") (class "Default")
      (node (ref "LED3") (pin "C") (pinfunction "C_C") (pintype "passive"))
      (node (ref "S3") (pin "4") (pinfunction "4_4") (pintype "passive"))
    )
    (net (code "65") (name "Net-(R3-Pad1)") (class "Default")
      (node (ref "R3") (pin "1") (pinfunction "1_1") (pintype "passive"))
      (node (ref "U1") (pin "3") (pinfunction "3_3") (pintype "bidirectional"))
    )
    (net (code "66") (name "Net-(R10-Pad1)") (class "Default")
      (node (ref "R10") (pin "1") (pinfunction "1_1") (pintype "passive"))
      (node (ref "U2") (pin "3") (pinfunction "3_3") (pintype "bidirectional"))
    )
    (net (code "67") (name "Net-(R15-Pad1)") (class "Default")
      (node (ref "R15") (pin "1") (pinfunction "1_1") (pintype "passive"))
      (node (ref "U5") (pin "3") (pinfunction "3_3") (pintype "bidirectional"))
    )
    (net (code "68") (name "unconnected-(IC1-DIAG-Pad11)") (class "Default")
      (node (ref "IC1") (pin "11") (pinfunction "DIAG_11") (pintype "bidirectional"))
    )
    (net (code "69") (name "unconnected-(IC1-INDEX-Pad12)") (class "Default")
      (node (ref "IC1") (pin "12") (pinfunction "INDEX_12") (pintype "bidirectional"))
    )
    (net (code "70") (name "unconnected-(IC2-DIAG-Pad11)") (class "Default")
      (node (ref "IC2") (pin "11") (pinfunction "DIAG_11") (pintype "bidirectional"))
    )
    (net (code "71") (name "unconnected-(IC2-INDEX-Pad12)") (class "Default")
      (node (ref "IC2") (pin "12") (pinfunction "INDEX_12") (pintype "bidirectional"))
    )
    (net (code "72") (name "unconnected-(IC4-DIAG-Pad11)") (class "Default")
      (node (ref "IC4") (pin "11") (pinfunction "DIAG_11") (pintype "bidirectional"))
    )
    (net (code "73") (name "unconnected-(IC4-INDEX-Pad12)") (class "Default")
      (node (ref "IC4") (pin "12") (pinfunction "INDEX_12") (pintype "bidirectional"))
    )
    (net (code "74") (name "unconnected-(JP3-Pad6)") (class "Default")
      (node (ref "JP3") (pin "6") (pinfunction "6_6") (pintype "passive"))
    )
    (net (code "75") (name "unconnected-(JP4-Pad4)") (class "Default")
      (node (ref "JP4") (pin "4") (pinfunction "4_4") (pintype "passive"))
    )
    (net (code "76") (name "unconnected-(JP4-Pad9)") (class "Default")
      (node (ref "JP4") (pin "9") (pinfunction "9_9") (pintype "passive"))
    )
    (net (code "77") (name "unconnected-(R1-Pad1)") (class "Default")
      (node (ref "R1") (pin "1") (pinfunction "1_1") (pintype "passive"))
    )
    (net (code "78") (name "unconnected-(R1-Pad2)") (class "Default")
      (node (ref "R1") (pin "2") (pinfunction "2_2") (pintype "passive"))
    )
    (net (code "79") (name "unconnected-(R2-Pad1)") (class "Default")
      (node (ref "R2") (pin "1") (pinfunction "1_1") (pintype "passive"))
    )
    (net (code "80") (name "unconnected-(R2-Pad2)") (class "Default")
      (node (ref "R2") (pin "2") (pinfunction "2_2") (pintype "passive"))
    )
    (net (code "81") (name "unconnected-(R7-Pad1)") (class "Default")
      (node (ref "R7") (pin "1") (pinfunction "1_1") (pintype "passive"))
    )
    (net (code "82") (name "unconnected-(R7-Pad2)") (class "Default")
      (node (ref "R7") (pin "2") (pinfunction "2_2") (pintype "passive"))
    )
    (net (code "83") (name "unconnected-(R8-Pad1)") (class "Default")
      (node (ref "R8") (pin "1") (pinfunction "1_1") (pintype "passive"))
    )
    (net (code "84") (name "unconnected-(R8-Pad2)") (class "Default")
      (node (ref "R8") (pin "2") (pinfunction "2_2") (pintype "passive"))
    )
    (net (code "85") (name "unconnected-(R12-Pad1)") (class "Default")
      (node (ref "R12") (pin "1") (pinfunction "1_1") (pintype "passive"))
    )
    (net (code "86") (name "unconnected-(R12-Pad2)") (class "Default")
      (node (ref "R12") (pin "2") (pinfunction "2_2") (pintype "passive"))
    )
    (net (code "87") (name "unconnected-(R13-Pad1)") (class "Default")
      (node (ref "R13") (pin "1") (pinfunction "1_1") (pintype "passive"))
    )
    (net (code "88") (name "unconnected-(R13-Pad2)") (class "Default")
      (node (ref "R13") (pin "2") (pinfunction "2_2") (pintype "passive"))
    )
    (net (code "89") (name "unconnected-(S1-4-PadP$2)") (class "Default")
      (node (ref "S1") (pin "P$2") (pinfunction "4_P$2") (pintype "passive"))
    )
    (net (code "90") (name "unconnected-(S3-Pad2)") (class "Default")
      (node (ref "S3") (pin "2") (pinfunction "2_2") (pintype "passive"))
    )
    (net (code "91") (name "unconnected-(S3-Pad3)") (class "Default")
      (node (ref "S3") (pin "3") (pinfunction "3_3") (pintype "passive"))
    )
  )
)
